# aircitizen-m5stack-v2.net
KiCad netlist of a schematic drawn in EAGLE
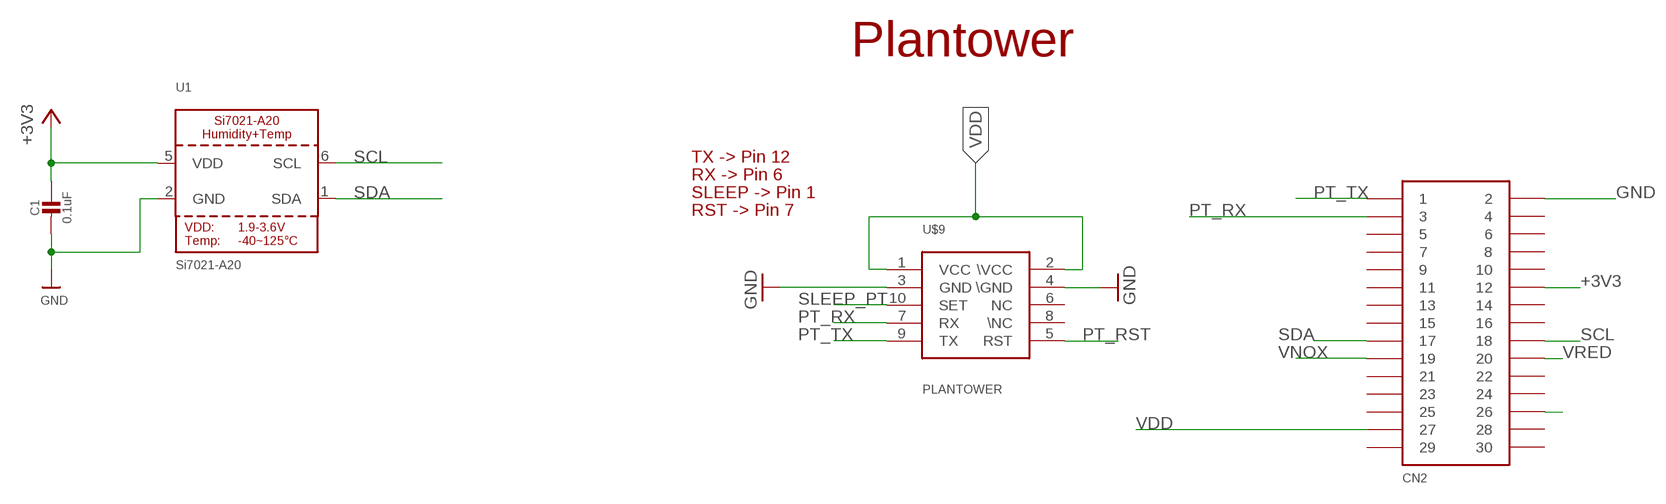
[diagram p0: schematic, sheet 1]
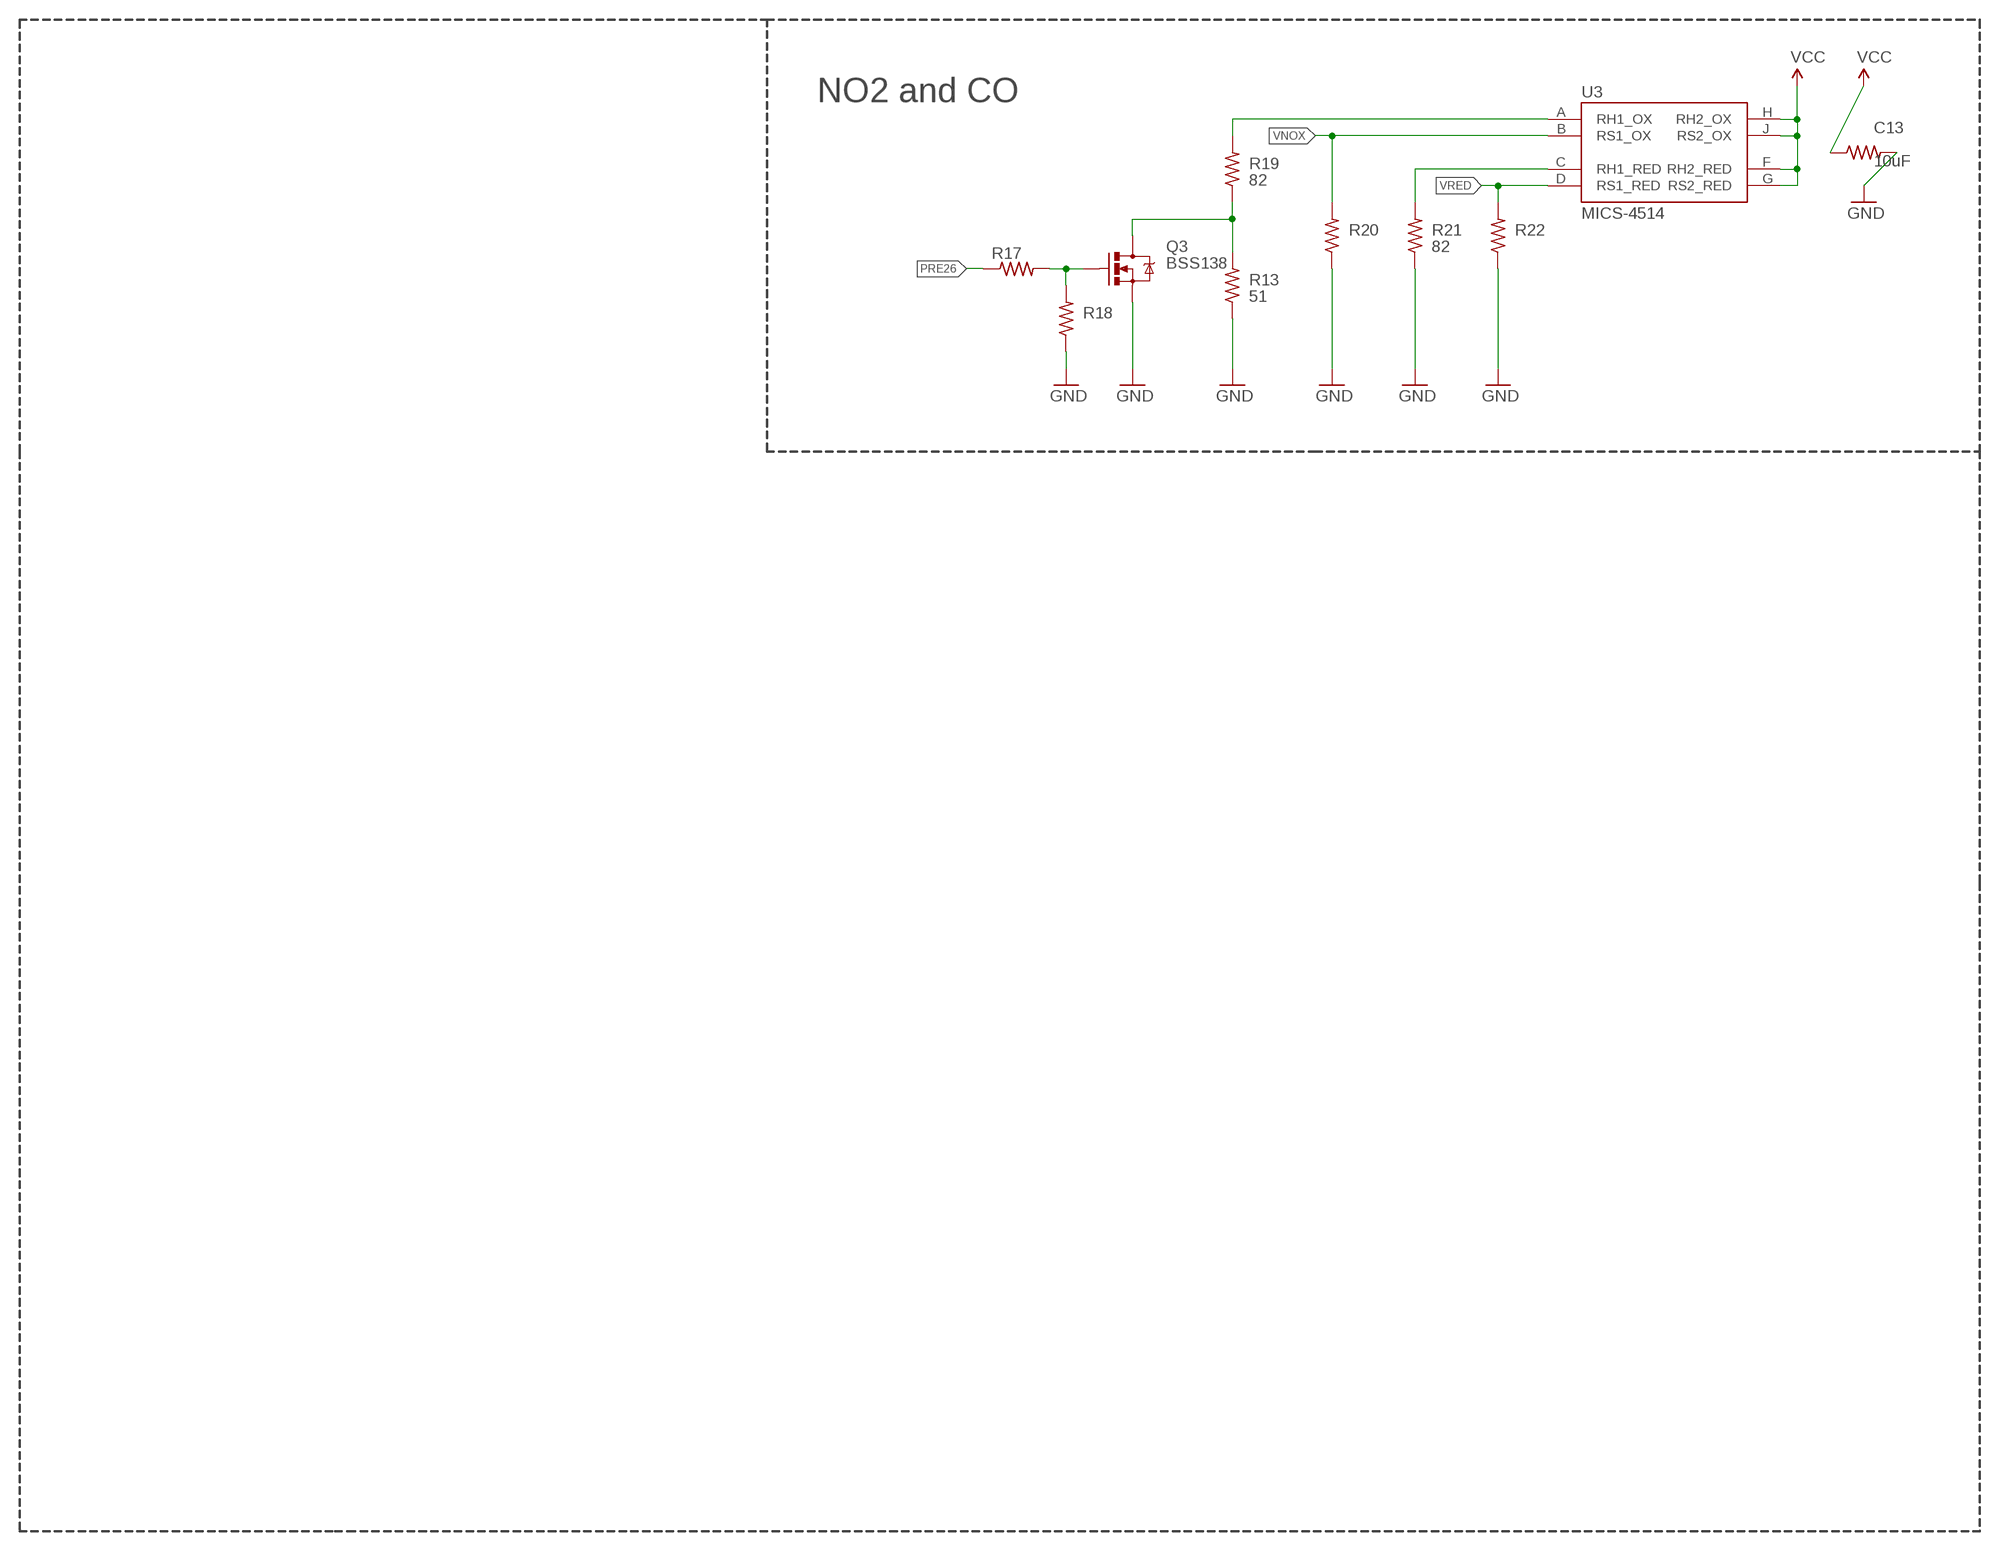
[diagram p1: schematic, sheet 2]

(export (version "E")
  (design (tool "Eeschema 10.0.6"))
  (components
    (comp (ref "C13")
      (value "10uF")
      (footprint "eagle-import:R1206FAB")
      (libsource (lib "eagle-import") (part "RES-US1206FAB"))
    )
    (comp (ref "Q3")
      (value "MOSFET-NCHANNELBSS138")
      (footprint "eagle-import:SOT23-3")
      (fields (field (name "P_NAME") "BSS138"))
      (libsource (lib "eagle-import") (part "MOSFET-NCHANNELBSS138"))
    )
    (comp (ref "R13")
      (value "51")
      (footprint "eagle-import:R1206FAB")
      (libsource (lib "eagle-import") (part "RES-US1206FAB"))
    )
    (comp (ref "R17")
      (value "100")
      (footprint "eagle-import:R1206FAB")
      (libsource (lib "eagle-import") (part "RES-US1206FAB"))
    )
    (comp (ref "R18")
      (value "100K")
      (footprint "eagle-import:R1206FAB")
      (libsource (lib "eagle-import") (part "RES-US1206FAB"))
    )
    (comp (ref "R19")
      (value "82")
      (footprint "eagle-import:R1206FAB")
      (libsource (lib "eagle-import") (part "RES-US1206FAB"))
    )
    (comp (ref "R20")
      (value "22K")
      (footprint "eagle-import:R1206FAB")
      (libsource (lib "eagle-import") (part "RES-US1206FAB"))
    )
    (comp (ref "R21")
      (value "82")
      (footprint "eagle-import:R1206FAB")
      (libsource (lib "eagle-import") (part "RES-US1206FAB"))
    )
    (comp (ref "R22")
      (value "47K")
      (footprint "eagle-import:R1206FAB")
      (libsource (lib "eagle-import") (part "RES-US1206FAB"))
    )
    (comp (ref "U3")
      (value "MICS-4514")
      (footprint "eagle-import:MICS_10-SMD")
      (libsource (lib "eagle-import") (part "MICS-4514"))
    )
    (comp (ref "C1")
      (value "0.1uF")
      (footprint "eagle-import:_1206")
      (libsource (lib "eagle-import") (part "CAP_CERAMIC_1206"))
    )
    (comp (ref "CN2")
      (value "CON_PINHD-2X15")
      (footprint "eagle-import:2X15SMD")
      (libsource (lib "eagle-import") (part "CON_PINHD-2X15"))
    )
    (comp (ref "U$9")
      (value "PLANTOWER")
      (footprint "eagle-import:CONN")
      (libsource (lib "eagle-import") (part "PLANTOWER"))
    )
    (comp (ref "U1")
      (value "Si7021-A20")
      (footprint "eagle-import:DFN6_3X3_SI")
      (libsource (lib "eagle-import") (part "SI7021-A20"))
    )
  )
  (nets
    (net (code "1") (name "+3V3") (class "Default")
      (node (ref "C1") (pin "1") (pinfunction "1_1") (pintype "passive"))
      (node (ref "CN2") (pin "P$12") (pinfunction "12_P$12") (pintype "bidirectional"))
      (node (ref "U1") (pin "5") (pinfunction "VDD_5") (pintype "power_in"))
    )
    (net (code "2") (name "GND") (class "Default")
      (node (ref "C1") (pin "2") (pinfunction "2_2") (pintype "passive"))
      (node (ref "C13") (pin "2") (pinfunction "2_2") (pintype "passive"))
      (node (ref "CN2") (pin "P$2") (pinfunction "2_P$2") (pintype "bidirectional"))
      (node (ref "Q3") (pin "2") (pinfunction "S_2") (pintype "passive"))
      (node (ref "R13") (pin "1") (pinfunction "1_1") (pintype "passive"))
      (node (ref "R18") (pin "1") (pinfunction "1_1") (pintype "passive"))
      (node (ref "R20") (pin "1") (pinfunction "1_1") (pintype "passive"))
      (node (ref "R21") (pin "1") (pinfunction "1_1") (pintype "passive"))
      (node (ref "R22") (pin "1") (pinfunction "1_1") (pintype "passive"))
      (node (ref "U$9") (pin "3") (pinfunction "GND_3") (pintype "bidirectional"))
      (node (ref "U$9") (pin "4") (pinfunction "\\GND_4") (pintype "bidirectional"))
      (node (ref "U1") (pin "2") (pinfunction "GND_2") (pintype "power_in"))
    )
    (net (code "3") (name "Net-(Q3-D)") (class "Default")
      (node (ref "Q3") (pin "3") (pinfunction "D_3") (pintype "passive"))
      (node (ref "R13") (pin "2") (pinfunction "2_2") (pintype "passive"))
      (node (ref "R19") (pin "1") (pinfunction "1_1") (pintype "passive"))
    )
    (net (code "4") (name "Net-(Q3-G)") (class "Default")
      (node (ref "Q3") (pin "1") (pinfunction "G_1") (pintype "passive"))
      (node (ref "R17") (pin "2") (pinfunction "2_2") (pintype "passive"))
      (node (ref "R18") (pin "2") (pinfunction "2_2") (pintype "passive"))
    )
    (net (code "5") (name "Net-(U3-RH1_OX)") (class "Default")
      (node (ref "R19") (pin "2") (pinfunction "2_2") (pintype "passive"))
      (node (ref "U3") (pin "A") (pinfunction "RH1_OX_A") (pintype "bidirectional"))
    )
    (net (code "6") (name "Net-(U3-RH1_RED)") (class "Default")
      (node (ref "R21") (pin "2") (pinfunction "2_2") (pintype "passive"))
      (node (ref "U3") (pin "C") (pinfunction "RH1_RED_C") (pintype "bidirectional"))
    )
    (net (code "7") (name "PRE26") (class "Default")
      (node (ref "CN2") (pin "P$26") (pinfunction "26_P$26") (pintype "bidirectional"))
      (node (ref "R17") (pin "1") (pinfunction "1_1") (pintype "passive"))
    )
    (net (code "8") (name "PT_RST") (class "Default")
      (node (ref "U$9") (pin "5") (pinfunction "RST_5") (pintype "bidirectional"))
    )
    (net (code "9") (name "PT_RX") (class "Default")
      (node (ref "CN2") (pin "P$3") (pinfunction "3_P$3") (pintype "bidirectional"))
      (node (ref "U$9") (pin "7") (pinfunction "RX_7") (pintype "bidirectional"))
    )
    (net (code "10") (name "PT_TX") (class "Default")
      (node (ref "CN2") (pin "P$1") (pinfunction "1_P$1") (pintype "bidirectional"))
      (node (ref "U$9") (pin "9") (pinfunction "TX_9") (pintype "bidirectional"))
    )
    (net (code "11") (name "SCL") (class "Default")
      (node (ref "CN2") (pin "P$18") (pinfunction "18_P$18") (pintype "bidirectional"))
      (node (ref "U1") (pin "6") (pinfunction "SCL_6") (pintype "open_collector"))
    )
    (net (code "12") (name "SDA") (class "Default")
      (node (ref "CN2") (pin "P$17") (pinfunction "17_P$17") (pintype "bidirectional"))
      (node (ref "U1") (pin "1") (pinfunction "SDA_1") (pintype "open_collector"))
    )
    (net (code "13") (name "SLEEP_PT") (class "Default")
      (node (ref "U$9") (pin "10") (pinfunction "SET_10") (pintype "bidirectional"))
    )
    (net (code "14") (name "VDD") (class "Default")
      (node (ref "C13") (pin "1") (pinfunction "1_1") (pintype "passive"))
      (node (ref "CN2") (pin "P$27") (pinfunction "27_P$27") (pintype "bidirectional"))
      (node (ref "U$9") (pin "1") (pinfunction "VCC_1") (pintype "bidirectional"))
      (node (ref "U$9") (pin "2") (pinfunction "\\VCC_2") (pintype "bidirectional"))
      (node (ref "U3") (pin "F") (pinfunction "RH2_RED_F") (pintype "bidirectional"))
      (node (ref "U3") (pin "G") (pinfunction "RS2_RED_G") (pintype "bidirectional"))
      (node (ref "U3") (pin "H") (pinfunction "RH2_OX_H") (pintype "bidirectional"))
      (node (ref "U3") (pin "J") (pinfunction "RS2_OX_J") (pintype "bidirectional"))
    )
    (net (code "15") (name "VNOX") (class "Default")
      (node (ref "CN2") (pin "P$19") (pinfunction "19_P$19") (pintype "bidirectional"))
      (node (ref "R20") (pin "2") (pinfunction "2_2") (pintype "passive"))
      (node (ref "U3") (pin "B") (pinfunction "RS1_OX_B") (pintype "bidirectional"))
    )
    (net (code "16") (name "VRED") (class "Default")
      (node (ref "CN2") (pin "P$20") (pinfunction "20_P$20") (pintype "bidirectional"))
      (node (ref "R22") (pin "2") (pinfunction "2_2") (pintype "passive"))
      (node (ref "U3") (pin "D") (pinfunction "RS1_RED_D") (pintype "bidirectional"))
    )
    (net (code "17") (name "unconnected-(CN2-4-PadP$4)") (class "Default")
      (node (ref "CN2") (pin "P$4") (pinfunction "4_P$4") (pintype "bidirectional"))
    )
    (net (code "18") (name "unconnected-(CN2-5-PadP$5)") (class "Default")
      (node (ref "CN2") (pin "P$5") (pinfunction "5_P$5") (pintype "bidirectional"))
    )
    (net (code "19") (name "unconnected-(CN2-6-PadP$6)") (class "Default")
      (node (ref "CN2") (pin "P$6") (pinfunction "6_P$6") (pintype "bidirectional"))
    )
    (net (code "20") (name "unconnected-(CN2-7-PadP$7)") (class "Default")
      (node (ref "CN2") (pin "P$7") (pinfunction "7_P$7") (pintype "bidirectional"))
    )
    (net (code "21") (name "unconnected-(CN2-8-PadP$8)") (class "Default")
      (node (ref "CN2") (pin "P$8") (pinfunction "8_P$8") (pintype "bidirectional"))
    )
    (net (code "22") (name "unconnected-(CN2-9-PadP$9)") (class "Default")
      (node (ref "CN2") (pin "P$9") (pinfunction "9_P$9") (pintype "bidirectional"))
    )
    (net (code "23") (name "unconnected-(CN2-10-PadP$10)") (class "Default")
      (node (ref "CN2") (pin "P$10") (pinfunction "10_P$10") (pintype "bidirectional"))
    )
    (net (code "24") (name "unconnected-(CN2-11-PadP$11)") (class "Default")
      (node (ref "CN2") (pin "P$11") (pinfunction "11_P$11") (pintype "bidirectional"))
    )
    (net (code "25") (name "unconnected-(CN2-13-PadP$13)") (class "Default")
      (node (ref "CN2") (pin "P$13") (pinfunction "13_P$13") (pintype "bidirectional"))
    )
    (net (code "26") (name "unconnected-(CN2-14-PadP$14)") (class "Default")
      (node (ref "CN2") (pin "P$14") (pinfunction "14_P$14") (pintype "bidirectional"))
    )
    (net (code "27") (name "unconnected-(CN2-15-PadP$15)") (class "Default")
      (node (ref "CN2") (pin "P$15") (pinfunction "15_P$15") (pintype "bidirectional"))
    )
    (net (code "28") (name "unconnected-(CN2-16-PadP$16)") (class "Default")
      (node (ref "CN2") (pin "P$16") (pinfunction "16_P$16") (pintype "bidirectional"))
    )
    (net (code "29") (name "unconnected-(CN2-21-PadP$21)") (class "Default")
      (node (ref "CN2") (pin "P$21") (pinfunction "21_P$21") (pintype "bidirectional"))
    )
    (net (code "30") (name "unconnected-(CN2-22-PadP$22)") (class "Default")
      (node (ref "CN2") (pin "P$22") (pinfunction "22_P$22") (pintype "bidirectional"))
    )
    (net (code "31") (name "unconnected-(CN2-23-PadP$23)") (class "Default")
      (node (ref "CN2") (pin "P$23") (pinfunction "23_P$23") (pintype "bidirectional"))
    )
    (net (code "32") (name "unconnected-(CN2-24-PadP$24)") (class "Default")
      (node (ref "CN2") (pin "P$24") (pinfunction "24_P$24") (pintype "bidirectional"))
    )
    (net (code "33") (name "unconnected-(CN2-25-PadP$25)") (class "Default")
      (node (ref "CN2") (pin "P$25") (pinfunction "25_P$25") (pintype "bidirectional"))
    )
    (net (code "34") (name "unconnected-(CN2-28-PadP$28)") (class "Default")
      (node (ref "CN2") (pin "P$28") (pinfunction "28_P$28") (pintype "bidirectional"))
    )
    (net (code "35") (name "unconnected-(CN2-29-PadP$29)") (class "Default")
      (node (ref "CN2") (pin "P$29") (pinfunction "29_P$29") (pintype "bidirectional"))
    )
    (net (code "36") (name "unconnected-(CN2-30-PadP$30)") (class "Default")
      (node (ref "CN2") (pin "P$30") (pinfunction "30_P$30") (pintype "bidirectional"))
    )
    (net (code "37") (name "unconnected-(U$9-NC-Pad6)") (class "Default")
      (node (ref "U$9") (pin "6") (pinfunction "NC_6") (pintype "bidirectional"))
    )
    (net (code "38") (name "unconnected-(U$9-\\NC-Pad8)") (class "Default")
      (node (ref "U$9") (pin "8") (pinfunction "\\NC_8") (pintype "bidirectional"))
    )
  )
)
